# LowKey.net
KiCad netlist of a schematic drawn in Altium Designer
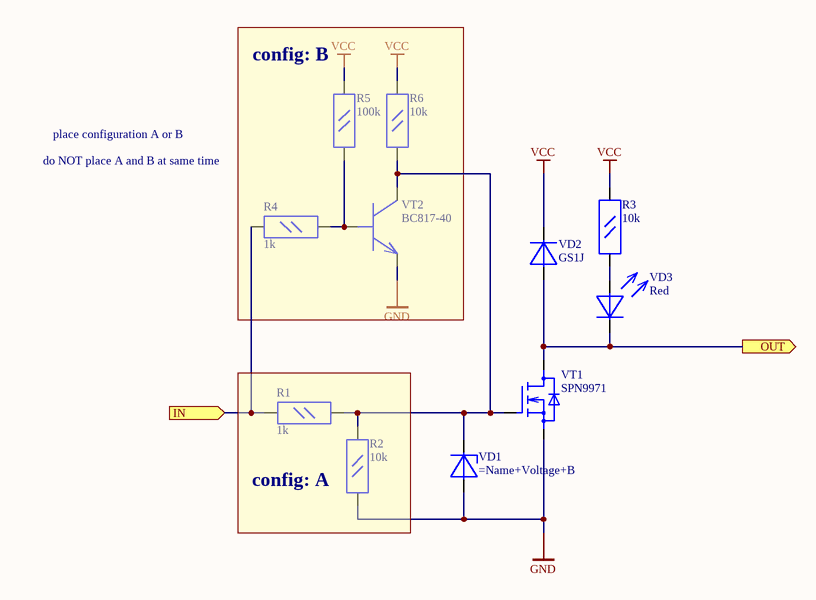
[diagram p0: LowKey.SchDoc]

(export (version "E")
  (design (tool "Eeschema 10.0.6"))
  (components
    (comp (ref "R1")
      (value "R0805")
      (footprint "RES0805")
      (description "Resistor")
      (fields (field (name "RESISTANCE (OHMS)") "1k"))
      (libsource (lib "zvemake_int_lib") (part "R0805"))
    )
    (comp (ref "R2")
      (value "R0805")
      (footprint "RES0805")
      (description "Resistor")
      (fields (field (name "RESISTANCE (OHMS)") "10k"))
      (libsource (lib "zvemake_int_lib") (part "R0805"))
    )
    (comp (ref "R3")
      (value "R0805")
      (footprint "RES0805")
      (description "Resistor")
      (fields (field (name "RESISTANCE (OHMS)") "10k"))
      (libsource (lib "zvemake_int_lib") (part "R0805"))
    )
    (comp (ref "R4")
      (value "R0805")
      (footprint "RES0805")
      (description "Resistor")
      (fields (field (name "RESISTANCE (OHMS)") "1k"))
      (libsource (lib "zvemake_int_lib") (part "R0805"))
    )
    (comp (ref "R5")
      (value "R0805")
      (footprint "RES0805")
      (description "Resistor")
      (fields (field (name "RESISTANCE (OHMS)") "100k"))
      (libsource (lib "zvemake_int_lib") (part "R0805"))
    )
    (comp (ref "R6")
      (value "R0805")
      (footprint "RES0805")
      (description "Resistor")
      (fields (field (name "RESISTANCE (OHMS)") "10k"))
      (libsource (lib "zvemake_int_lib") (part "R0805"))
    )
    (comp (ref "VD1")
      (value "PDZ12")
      (footprint "SOD323")
      (description "Diode")
      (fields (field (name "VOLTAGE") "12"))
      (libsource (lib "zvemake_int_lib") (part "PDZ-B"))
    )
    (comp (ref "VD2")
      (value "GS1J")
      (footprint "DO-214AC(SMA)")
      (description "1.0A Surface Mount Standard Diode")
      (fields (field (name "VOLTAGE") "600V") (field (name "MANUFACTURER") "WTE"))
      (libsource (lib "zvemake_int_lib") (part "GS1J"))
    )
    (comp (ref "VD3")
      (value "Led Red 3mm")
      (footprint "3mm led red")
      (description "3mm Red Led 2.54pitch")
      (fields (field (name "COLOR") "Red"))
      (libsource (lib "zvemake_int_lib") (part "Led Red 3mm"))
    )
    (comp (ref "VT1")
      (value "SPN9971")
      (footprint "DPAK")
      (description "N-channel MOSFET transistor")
      (libsource (lib "zvemake_int_lib") (part "SPN9971"))
    )
    (comp (ref "VT2")
      (value "BC817-40")
      (footprint "SOT95P230X110-3N")
      (description "NPN bipolar transistor")
      (libsource (lib "zvemake_int_lib") (part "BC817-40"))
    )
  )
  (nets
    (net (code "1") (name "/IN") (class "Default")
      (node (ref "R1") (pin "1") (pinfunction "1_1") (pintype "passive"))
      (node (ref "R4") (pin "1") (pinfunction "1_1") (pintype "passive"))
    )
    (net (code "2") (name "/OUT") (class "Default")
      (node (ref "VD2") (pin "2") (pinfunction "A_2") (pintype "passive"))
      (node (ref "VD3") (pin "1") (pinfunction "C_1") (pintype "passive"))
      (node (ref "VT1") (pin "2") (pinfunction "D_2") (pintype "passive"))
    )
    (net (code "3") (name "GND") (class "Default")
      (node (ref "R2") (pin "1") (pinfunction "1_1") (pintype "passive"))
      (node (ref "VD1") (pin "2") (pinfunction "A_2") (pintype "passive"))
      (node (ref "VT1") (pin "3") (pinfunction "S_3") (pintype "passive"))
      (node (ref "VT2") (pin "2") (pinfunction "E_2") (pintype "passive"))
    )
    (net (code "4") (name "Net-(VD1-C)") (class "Default")
      (node (ref "R1") (pin "2") (pinfunction "2_2") (pintype "passive"))
      (node (ref "R2") (pin "2") (pinfunction "2_2") (pintype "passive"))
      (node (ref "R6") (pin "1") (pinfunction "1_1") (pintype "passive"))
      (node (ref "VD1") (pin "1") (pinfunction "C_1") (pintype "passive"))
      (node (ref "VT1") (pin "1") (pinfunction "G_1") (pintype "passive"))
      (node (ref "VT2") (pin "3") (pinfunction "C_3") (pintype "passive"))
    )
    (net (code "5") (name "Net-(VD3-A)") (class "Default")
      (node (ref "R3") (pin "1") (pinfunction "1_1") (pintype "passive"))
      (node (ref "VD3") (pin "2") (pinfunction "A_2") (pintype "passive"))
    )
    (net (code "6") (name "Net-(VT2-B)") (class "Default")
      (node (ref "R4") (pin "2") (pinfunction "2_2") (pintype "passive"))
      (node (ref "R5") (pin "1") (pinfunction "1_1") (pintype "passive"))
      (node (ref "VT2") (pin "1") (pinfunction "B_1") (pintype "passive"))
    )
    (net (code "7") (name "VCC") (class "Default")
      (node (ref "R3") (pin "2") (pinfunction "2_2") (pintype "passive"))
      (node (ref "R5") (pin "2") (pinfunction "2_2") (pintype "passive"))
      (node (ref "R6") (pin "2") (pinfunction "2_2") (pintype "passive"))
      (node (ref "VD2") (pin "1") (pinfunction "C_1") (pintype "passive"))
    )
  )
)
